# DM1097_RIGHT_OV9282.net
KiCad netlist of a schematic drawn in Altium Designer
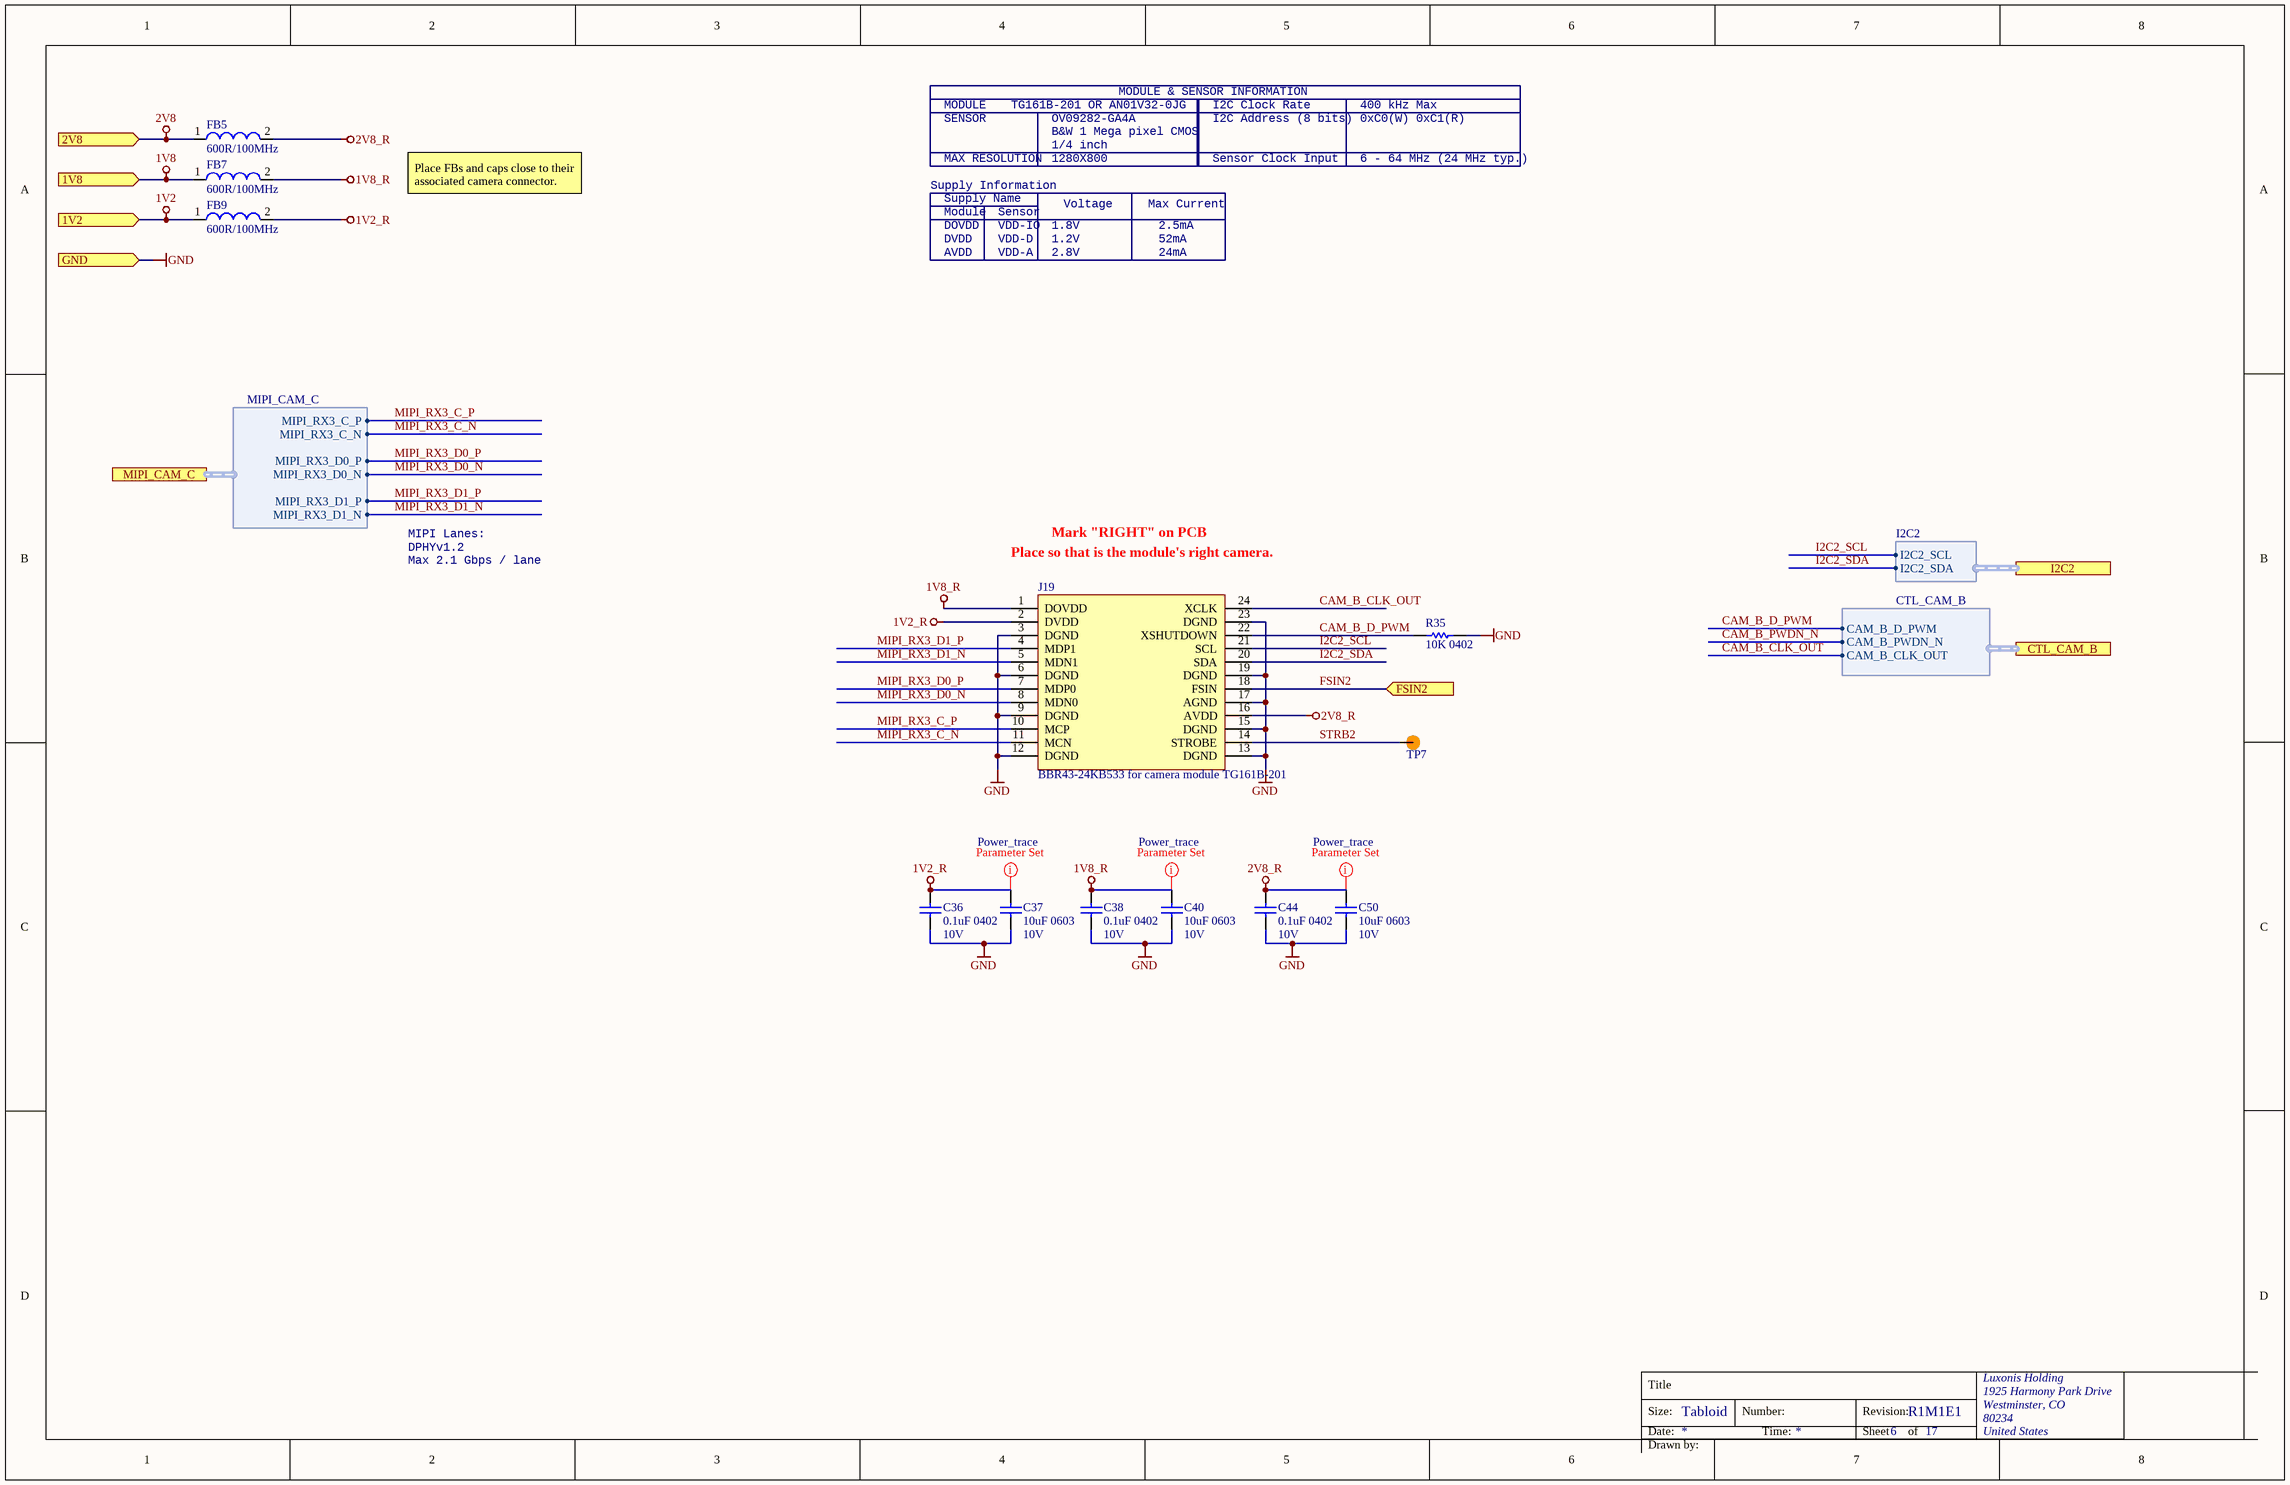
[diagram p0: DM1097_RIGHT_OV9282.SchDoc]

(export (version "E")
  (design (tool "Eeschema 10.0.6"))
  (components
    (comp (ref "C36")
      (value "0.1uF 0402")
      (footprint "CAP_Altium_Vault_Generic:CAPC0402(1005)70_N")
      (description "CAP CER 0.1UF 10V X7R 0402 5%")
      (fields (field (name "TOLERANCE") "5%") (field (name "VOLTAGE RATING") "10V"))
      (libsource (lib "LuxonisMaster") (part "GRM155R71A104JA01D"))
    )
    (comp (ref "C37")
      (value "10uF 0603")
      (footprint "CAP_Altium_Vault_Generic:CAPC0603(1608)100_N")
      (description "CAP CER 10UF 10V X5R 0603 20%")
      (fields (field (name "TOLERANCE") "20%") (field (name "VOLTAGE RATING") "10V"))
      (libsource (lib "LuxonisMaster") (part "GRM188R61A106ME69D"))
    )
    (comp (ref "C38")
      (value "0.1uF 0402")
      (footprint "CAP_Altium_Vault_Generic:CAPC0402(1005)70_N")
      (description "CAP CER 0.1UF 10V X7R 0402 5%")
      (fields (field (name "TOLERANCE") "5%") (field (name "VOLTAGE RATING") "10V"))
      (libsource (lib "LuxonisMaster") (part "GRM155R71A104JA01D"))
    )
    (comp (ref "C40")
      (value "10uF 0603")
      (footprint "CAP_Altium_Vault_Generic:CAPC0603(1608)100_N")
      (description "CAP CER 10UF 10V X5R 0603 20%")
      (fields (field (name "TOLERANCE") "20%") (field (name "VOLTAGE RATING") "10V"))
      (libsource (lib "LuxonisMaster") (part "GRM188R61A106ME69D"))
    )
    (comp (ref "C44")
      (value "0.1uF 0402")
      (footprint "CAP_Altium_Vault_Generic:CAPC0402(1005)70_N")
      (description "CAP CER 0.1UF 10V X7R 0402 5%")
      (fields (field (name "TOLERANCE") "5%") (field (name "VOLTAGE RATING") "10V"))
      (libsource (lib "LuxonisMaster") (part "GRM155R71A104JA01D"))
    )
    (comp (ref "C50")
      (value "10uF 0603")
      (footprint "CAP_Altium_Vault_Generic:CAPC0603(1608)100_N")
      (description "CAP CER 10UF 10V X5R 0603 20%")
      (fields (field (name "TOLERANCE") "20%") (field (name "VOLTAGE RATING") "10V"))
      (libsource (lib "LuxonisMaster") (part "GRM188R61A106ME69D"))
    )
    (comp (ref "FB5")
      (value "600R/100MHz")
      (footprint "LuxonisMaster:2508056017Y2")
      (description "FERRITE BEAD, 0.1OHM, 2A, 0805, 600R/100MHz")
      (fields (field (name "TOLERANCE") "25%"))
      (libsource (lib "LuxonisMaster") (part "2508056017Y2"))
    )
    (comp (ref "FB7")
      (value "600R/100MHz")
      (footprint "LuxonisMaster:2508056017Y2")
      (description "FERRITE BEAD, 0.1OHM, 2A, 0805, 600R/100MHz")
      (fields (field (name "TOLERANCE") "25%"))
      (libsource (lib "LuxonisMaster") (part "2508056017Y2"))
    )
    (comp (ref "FB9")
      (value "600R/100MHz")
      (footprint "LuxonisMaster:2508056017Y2")
      (description "FERRITE BEAD, 0.1OHM, 2A, 0805, 600R/100MHz")
      (fields (field (name "TOLERANCE") "25%"))
      (libsource (lib "LuxonisMaster") (part "2508056017Y2"))
    )
    (comp (ref "J19")
      (value "BBR43-24KB533 for camera module TG161B-201")
      (footprint "LuxonisMaster:TG161B-201 / AN01V32 - Board Wrap (7mm setback) MinPads")
      (description "CONN 24 way, 2 row board to board connector SMD")
      (libsource (lib "LuxonisMaster") (part "TG161B-201_Connector"))
    )
    (comp (ref "R35")
      (value "10K 0402")
      (footprint "RES_Altium_Vault_Generic:RESC0402(1005)_N")
      (fields (field (name "TOLERANCE") "1%"))
      (libsource (lib "LuxonisMaster") (part "RC0402FR-1310KL"))
    )
    (comp (ref "TP7")
      (value "TP100_200_NS")
      (footprint "LuxonisMaster:TP100_200_NS")
      (libsource (lib "LuxonisMaster") (part "TEST_POINT"))
    )
  )
  (nets
    (net (code "4") (name "/CAM_B_CLK_OUT") (class "Default")
      (node (ref "J19") (pin "24") (pinfunction "XCLK_24") (pintype "passive"))
    )
    (net (code "5") (name "/CAM_B_D_PWM") (class "Default")
      (node (ref "J19") (pin "22") (pinfunction "XSHUTDOWN_22") (pintype "passive"))
      (node (ref "R35") (pin "1") (pinfunction "1_1") (pintype "passive"))
    )
    (net (code "7") (name "/FSIN2") (class "Default")
      (node (ref "J19") (pin "18") (pinfunction "FSIN_18") (pintype "passive"))
    )
    (net (code "8") (name "/I2C2_SCL") (class "Default")
      (node (ref "J19") (pin "21") (pinfunction "SCL_21") (pintype "passive"))
    )
    (net (code "9") (name "/I2C2_SDA") (class "Default")
      (node (ref "J19") (pin "20") (pinfunction "SDA_20") (pintype "passive"))
    )
    (net (code "10") (name "/MIPI_RX3_C_N") (class "Default")
      (node (ref "J19") (pin "11") (pinfunction "MCN_11") (pintype "passive"))
    )
    (net (code "11") (name "/MIPI_RX3_C_P") (class "Default")
      (node (ref "J19") (pin "10") (pinfunction "MCP_10") (pintype "passive"))
    )
    (net (code "12") (name "/MIPI_RX3_D0_N") (class "Default")
      (node (ref "J19") (pin "8") (pinfunction "MDN0_8") (pintype "passive"))
    )
    (net (code "13") (name "/MIPI_RX3_D0_P") (class "Default")
      (node (ref "J19") (pin "7") (pinfunction "MDP0_7") (pintype "passive"))
    )
    (net (code "14") (name "/MIPI_RX3_D1_N") (class "Default")
      (node (ref "J19") (pin "5") (pinfunction "MDN1_5") (pintype "passive"))
    )
    (net (code "15") (name "/MIPI_RX3_D1_P") (class "Default")
      (node (ref "J19") (pin "4") (pinfunction "MDP1_4") (pintype "passive"))
    )
    (net (code "16") (name "/STRB2") (class "Default")
      (node (ref "J19") (pin "14") (pinfunction "STROBE_14") (pintype "passive"))
      (node (ref "TP7") (pin "1") (pintype "passive"))
    )
    (net (code "20") (name "1V2") (class "Default")
      (node (ref "FB9") (pin "1") (pinfunction "1_1") (pintype "passive"))
    )
    (net (code "21") (name "1V2_R") (class "Default")
      (node (ref "C36") (pin "2") (pinfunction "2_2") (pintype "passive"))
      (node (ref "C37") (pin "2") (pinfunction "2_2") (pintype "passive"))
      (node (ref "FB9") (pin "2") (pinfunction "2_2") (pintype "passive"))
      (node (ref "J19") (pin "2") (pinfunction "DVDD_2") (pintype "passive"))
    )
    (net (code "22") (name "1V8") (class "Default")
      (node (ref "FB7") (pin "1") (pinfunction "1_1") (pintype "passive"))
    )
    (net (code "23") (name "1V8_R") (class "Default")
      (node (ref "C38") (pin "2") (pinfunction "2_2") (pintype "passive"))
      (node (ref "C40") (pin "2") (pinfunction "2_2") (pintype "passive"))
      (node (ref "FB7") (pin "2") (pinfunction "2_2") (pintype "passive"))
      (node (ref "J19") (pin "1") (pinfunction "DOVDD_1") (pintype "passive"))
    )
    (net (code "24") (name "2V8") (class "Default")
      (node (ref "FB5") (pin "1") (pinfunction "1_1") (pintype "passive"))
    )
    (net (code "25") (name "2V8_R") (class "Default")
      (node (ref "C44") (pin "2") (pinfunction "2_2") (pintype "passive"))
      (node (ref "C50") (pin "2") (pinfunction "2_2") (pintype "passive"))
      (node (ref "FB5") (pin "2") (pinfunction "2_2") (pintype "passive"))
      (node (ref "J19") (pin "16") (pinfunction "AVDD_16") (pintype "passive"))
    )
    (net (code "26") (name "GND") (class "Default")
      (node (ref "C36") (pin "1") (pinfunction "1_1") (pintype "passive"))
      (node (ref "C37") (pin "1") (pinfunction "1_1") (pintype "passive"))
      (node (ref "C38") (pin "1") (pinfunction "1_1") (pintype "passive"))
      (node (ref "C40") (pin "1") (pinfunction "1_1") (pintype "passive"))
      (node (ref "C44") (pin "1") (pinfunction "1_1") (pintype "passive"))
      (node (ref "C50") (pin "1") (pinfunction "1_1") (pintype "passive"))
      (node (ref "J19") (pin "12") (pinfunction "DGND_12") (pintype "passive"))
      (node (ref "J19") (pin "13") (pinfunction "DGND_13") (pintype "passive"))
      (node (ref "J19") (pin "15") (pinfunction "DGND_15") (pintype "passive"))
      (node (ref "J19") (pin "17") (pinfunction "AGND_17") (pintype "passive"))
      (node (ref "J19") (pin "19") (pinfunction "DGND_19") (pintype "passive"))
      (node (ref "J19") (pin "23") (pinfunction "DGND_23") (pintype "passive"))
      (node (ref "J19") (pin "3") (pinfunction "DGND_3") (pintype "passive"))
      (node (ref "J19") (pin "6") (pinfunction "DGND_6") (pintype "passive"))
      (node (ref "J19") (pin "9") (pinfunction "DGND_9") (pintype "passive"))
      (node (ref "R35") (pin "2") (pinfunction "2_2") (pintype "passive"))
    )
  )
)
